# USB-TO-UART-BRIDGE.net
KiCad netlist of a schematic drawn in Altium Designer
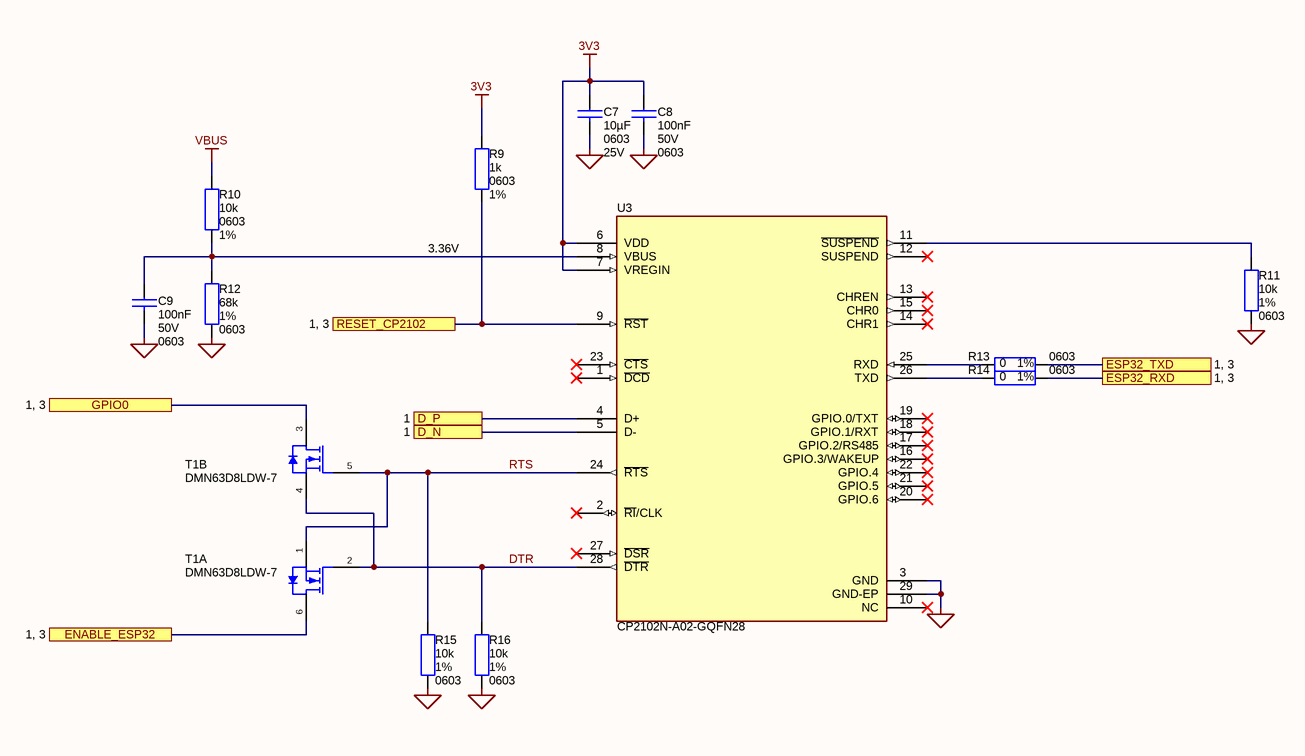
[diagram p0: USB-TO-UART-BRIDGE.SchDoc]

(export (version "E")
  (design (tool "Eeschema 10.0.6"))
  (components
    (comp (ref "C7")
      (value "10µF")
      (footprint "CAPC0603X37L")
      (description "CAPACITOR 10 µF 0603 X5R 25V 10%")
      (fields
        (field (name "MANUFACTURER 1 PART NUMBER") "GRM188R61E106KA73D")
        (field (name "CASE/PACKAGE") "0603")
        (field (name "VOLTAGE") "25V")
        (field (name "TOLERANCE") "10%")
        (field (name "COMMENT DESIGNER") "can be substituted same values other manufacturer")
      )
      (libsource (lib "EDATRON Solutions GmbH") (part "C"))
    )
    (comp (ref "C8")
      (value "100nF")
      (footprint "CAPC0603X37L")
      (description "CAPACITOR 100 nF 0603 X7R 50V 10%")
      (fields
        (field (name "VOLTAGE") "50V")
        (field (name "MANUFACTURER 1 PART NUMBER") "C0603C104K5RACTU")
        (field (name "TOLERANCE") "10%")
        (field (name "CASE/PACKAGE") "0603")
        (field (name "COMMENT DESIGNER") "can be substituted same values other manufacturer")
      )
      (libsource (lib "EDATRON Solutions GmbH") (part "C"))
    )
    (comp (ref "C9")
      (value "100nF")
      (footprint "CAPC0603X37L")
      (description "CAPACITOR 100 nF 0603 X7R 50V 10%")
      (fields
        (field (name "VOLTAGE") "50V")
        (field (name "MANUFACTURER 1 PART NUMBER") "C0603C104K5RACTU")
        (field (name "TOLERANCE") "10%")
        (field (name "CASE/PACKAGE") "0603")
        (field (name "COMMENT DESIGNER") "can be substituted same values other manufacturer")
      )
      (libsource (lib "EDATRON Solutions GmbH") (part "C"))
    )
    (comp (ref "R9")
      (value "1k")
      (footprint "RESC0603X21L")
      (description "RESISTOR 1K 1% 0603 100mW")
      (fields
        (field (name "CASE/PACKAGE") "0603")
        (field (name "MANUFACTURER 1 PART NUMBER") "RC0603FR-071KL")
        (field (name "POWER") "100mW")
        (field (name "TOLERANCE") "1%")
        (field (name "COMMENT DESIGNER") "can be substituted same values other manufacturers")
      )
      (libsource (lib "") (part "R_1"))
    )
    (comp (ref "R10")
      (value "10k")
      (footprint "RESC0603X21L")
      (description "RESISTOR 33K 1% 0603 100mW")
      (fields
        (field (name "MANUFACTURER 1 PART NUMBER") "RC0603FR-0733KL")
        (field (name "POWER") "100mW")
        (field (name "CASE/PACKAGE") "0603")
        (field (name "TOLERANCE") "1%")
        (field (name "COMMENT DESIGNER") "can be substituted same values other manufacturers")
      )
      (libsource (lib "") (part "R_1"))
    )
    (comp (ref "R11")
      (value "10k")
      (footprint "RESC0603X21L")
      (description "RESISTOR 10K 1% 0603 100mW")
      (fields
        (field (name "POWER") "100mW")
        (field (name "TOLERANCE") "1%")
        (field (name "CASE/PACKAGE") "0603")
        (field (name "MANUFACTURER 1 PART NUMBER") "RC0603FR-0710KL")
        (field (name "COMMENT DESIGNER") "can be substituted same values other manufacturers")
      )
      (libsource (lib "") (part "R_2"))
    )
    (comp (ref "R12")
      (value "68k")
      (footprint "RESC0603X21L")
      (description "RESISTOR 68K 1% 0603 100mW")
      (fields
        (field (name "TOLERANCE") "1%")
        (field (name "MANUFACTURER 1 PART NUMBER") "RC0603FR-0768KL")
        (field (name "POWER") "100mW")
        (field (name "CASE/PACKAGE") "0603")
        (field (name "COMMENT DESIGNER") "can be substituted same values other manufacturers")
      )
      (libsource (lib "") (part "R_1"))
    )
    (comp (ref "R13")
      (value "0")
      (footprint "RESC0603X21L")
      (description "RESISTOR 0R 1% 0603 100mW")
      (fields
        (field (name "POWER") "100mW")
        (field (name "CASE/PACKAGE") "0603")
        (field (name "MANUFACTURER 1 PART NUMBER") "RC0603FR-070RL")
        (field (name "TOLERANCE") "1%")
        (field (name "COMMENT DESIGNER") "can be substituted same values other manufacturers")
      )
      (libsource (lib "EDATRON Solutions GmbH") (part "R"))
    )
    (comp (ref "R14")
      (value "0")
      (footprint "RESC0603X21L")
      (description "RESISTOR 0R 1% 0603 100mW")
      (fields
        (field (name "POWER") "100mW")
        (field (name "CASE/PACKAGE") "0603")
        (field (name "MANUFACTURER 1 PART NUMBER") "RC0603FR-070RL")
        (field (name "TOLERANCE") "1%")
        (field (name "COMMENT DESIGNER") "can be substituted same values other manufacturers")
      )
      (libsource (lib "EDATRON Solutions GmbH") (part "R"))
    )
    (comp (ref "R15")
      (value "10k")
      (footprint "RESC0603X21L")
      (description "RESISTOR 10K 1% 0603 100mW")
      (fields
        (field (name "POWER") "100mW")
        (field (name "TOLERANCE") "1%")
        (field (name "CASE/PACKAGE") "0603")
        (field (name "MANUFACTURER 1 PART NUMBER") "RC0603FR-0710KL")
        (field (name "COMMENT DESIGNER") "can be substituted same values other manufacturers")
      )
      (libsource (lib "") (part "R_2"))
    )
    (comp (ref "R16")
      (value "10k")
      (footprint "RESC0603X21L")
      (description "RESISTOR 10K 1% 0603 100mW")
      (fields
        (field (name "POWER") "100mW")
        (field (name "TOLERANCE") "1%")
        (field (name "CASE/PACKAGE") "0603")
        (field (name "MANUFACTURER 1 PART NUMBER") "RC0603FR-0710KL")
        (field (name "COMMENT DESIGNER") "can be substituted same values other manufacturers")
      )
      (libsource (lib "") (part "R_2"))
    )
    (comp (ref "T1")
      (value "DMN63D8LDW-7")
      (footprint "SOT23-6P65_210X110L32X20")
      (fields (field (name "POWER") "400"))
      (libsource (lib "EDATRON Solutions GmbH") (part "DUAL-MOSFET-N"))
    )
    (comp (ref "U3")
      (value "CP2102N-A02-GQFN28")
      (footprint "CP2102N-A02-GQFN28-Footprint-1")
      (description "USB-IC-Schnittstelle USBXpress - USB to UART Bridge QFN28")
      (libsource (lib "EDATRON Solutions GmbH") (part "CP2102N-A02-GQFN28"))
    )
  )
  (nets
    (net (code "1") (name "/DTR") (class "Default")
      (node (ref "R16") (pin "2") (pinfunction "2_2") (pintype "passive"))
      (node (ref "T1") (pin "2") (pinfunction "G1_2") (pintype "passive"))
      (node (ref "T1") (pin "4") (pinfunction "S2_4") (pintype "passive"))
      (node (ref "U3") (pin "28") (pinfunction "~{DTR}_28") (pintype "output"))
    )
    (net (code "2") (name "/D_N") (class "Default")
      (node (ref "U3") (pin "5") (pinfunction "D-_5") (pintype "passive"))
    )
    (net (code "3") (name "/D_P") (class "Default")
      (node (ref "U3") (pin "4") (pinfunction "D+_4") (pintype "passive"))
    )
    (net (code "4") (name "/ENABLE_ESP32") (class "Default")
      (node (ref "T1") (pin "6") (pinfunction "D1_6") (pintype "passive"))
    )
    (net (code "5") (name "/ESP32_RXD") (class "Default")
      (node (ref "R14") (pin "1") (pinfunction "1_1") (pintype "passive"))
    )
    (net (code "6") (name "/ESP32_TXD") (class "Default")
      (node (ref "R13") (pin "1") (pinfunction "1_1") (pintype "passive"))
    )
    (net (code "7") (name "/GPIO0") (class "Default")
      (node (ref "T1") (pin "3") (pinfunction "D2_3") (pintype "passive"))
    )
    (net (code "8") (name "/RESET_CP2102") (class "Default")
      (node (ref "R9") (pin "2") (pinfunction "2_2") (pintype "passive"))
      (node (ref "U3") (pin "9") (pinfunction "~{RST}_9") (pintype "input"))
    )
    (net (code "9") (name "/RTS") (class "Default")
      (node (ref "R15") (pin "2") (pinfunction "2_2") (pintype "passive"))
      (node (ref "T1") (pin "1") (pinfunction "S1_1") (pintype "passive"))
      (node (ref "T1") (pin "5") (pinfunction "G2_5") (pintype "passive"))
      (node (ref "U3") (pin "24") (pinfunction "~{RTS}_24") (pintype "output"))
    )
    (net (code "10") (name "3V3") (class "Default")
      (node (ref "C7") (pin "1") (pinfunction "1_1") (pintype "passive"))
      (node (ref "C8") (pin "1") (pinfunction "1_1") (pintype "passive"))
      (node (ref "R9") (pin "1") (pinfunction "1_1") (pintype "passive"))
      (node (ref "U3") (pin "6") (pinfunction "VDD_6") (pintype "power_in"))
      (node (ref "U3") (pin "7") (pinfunction "VREGIN_7") (pintype "input"))
    )
    (net (code "11") (name "GND") (class "Default")
      (node (ref "C7") (pin "2") (pinfunction "2_2") (pintype "passive"))
      (node (ref "C8") (pin "2") (pinfunction "2_2") (pintype "passive"))
      (node (ref "C9") (pin "2") (pinfunction "2_2") (pintype "passive"))
      (node (ref "R11") (pin "1") (pinfunction "1_1") (pintype "passive"))
      (node (ref "R12") (pin "2") (pinfunction "2_2") (pintype "passive"))
      (node (ref "R15") (pin "1") (pinfunction "1_1") (pintype "passive"))
      (node (ref "R16") (pin "1") (pinfunction "1_1") (pintype "passive"))
      (node (ref "U3") (pin "29") (pinfunction "GND-EP_29") (pintype "power_in"))
      (node (ref "U3") (pin "3") (pinfunction "GND_3") (pintype "power_in"))
    )
    (net (code "12") (name "Net-(U3-RXD)") (class "Default")
      (node (ref "R13") (pin "2") (pinfunction "2_2") (pintype "passive"))
      (node (ref "U3") (pin "25") (pinfunction "RXD_25") (pintype "input"))
    )
    (net (code "13") (name "Net-(U3-TXD)") (class "Default")
      (node (ref "R14") (pin "2") (pinfunction "2_2") (pintype "passive"))
      (node (ref "U3") (pin "26") (pinfunction "TXD_26") (pintype "output"))
    )
    (net (code "14") (name "Net-(U3-VBUS)") (class "Default")
      (node (ref "C9") (pin "1") (pinfunction "1_1") (pintype "passive"))
      (node (ref "R10") (pin "2") (pinfunction "2_2") (pintype "passive"))
      (node (ref "R12") (pin "1") (pinfunction "1_1") (pintype "passive"))
      (node (ref "U3") (pin "8") (pinfunction "VBUS_8") (pintype "input"))
    )
    (net (code "15") (name "Net-(U3-~{SUSPEND})") (class "Default")
      (node (ref "R11") (pin "2") (pinfunction "2_2") (pintype "passive"))
      (node (ref "U3") (pin "11") (pinfunction "~{SUSPEND}_11") (pintype "output"))
    )
    (net (code "16") (name "VBUS") (class "Default")
      (node (ref "R10") (pin "1") (pinfunction "1_1") (pintype "passive"))
    )
    (net (code "17") (name "unconnected-(U3-CHR0-Pad15)") (class "Default")
      (node (ref "U3") (pin "15") (pinfunction "CHR0_15") (pintype "output+no_connect"))
    )
    (net (code "18") (name "unconnected-(U3-CHR1-Pad14)") (class "Default")
      (node (ref "U3") (pin "14") (pinfunction "CHR1_14") (pintype "output+no_connect"))
    )
    (net (code "19") (name "unconnected-(U3-CHREN-Pad13)") (class "Default")
      (node (ref "U3") (pin "13") (pinfunction "CHREN_13") (pintype "output+no_connect"))
    )
    (net (code "20") (name "unconnected-(U3-GPIO.0{slash}TXT-Pad19)") (class "Default")
      (node (ref "U3") (pin "19") (pinfunction "GPIO.0/TXT_19") (pintype "bidirectional+no_connect"))
    )
    (net (code "21") (name "unconnected-(U3-GPIO.1{slash}RXT-Pad18)") (class "Default")
      (node (ref "U3") (pin "18") (pinfunction "GPIO.1/RXT_18") (pintype "bidirectional+no_connect"))
    )
    (net (code "22") (name "unconnected-(U3-GPIO.2{slash}RS485-Pad17)") (class "Default")
      (node (ref "U3") (pin "17") (pinfunction "GPIO.2/RS485_17") (pintype "bidirectional+no_connect"))
    )
    (net (code "23") (name "unconnected-(U3-GPIO.3{slash}WAKEUP-Pad16)") (class "Default")
      (node (ref "U3") (pin "16") (pinfunction "GPIO.3/WAKEUP_16") (pintype "bidirectional+no_connect"))
    )
    (net (code "24") (name "unconnected-(U3-GPIO.4-Pad22)") (class "Default")
      (node (ref "U3") (pin "22") (pinfunction "GPIO.4_22") (pintype "bidirectional+no_connect"))
    )
    (net (code "25") (name "unconnected-(U3-GPIO.5-Pad21)") (class "Default")
      (node (ref "U3") (pin "21") (pinfunction "GPIO.5_21") (pintype "bidirectional+no_connect"))
    )
    (net (code "26") (name "unconnected-(U3-GPIO.6-Pad20)") (class "Default")
      (node (ref "U3") (pin "20") (pinfunction "GPIO.6_20") (pintype "bidirectional+no_connect"))
    )
    (net (code "27") (name "unconnected-(U3-NC-Pad10)") (class "Default")
      (node (ref "U3") (pin "10") (pinfunction "NC_10") (pintype "passive+no_connect"))
    )
    (net (code "28") (name "unconnected-(U3-SUSPEND-Pad12)") (class "Default")
      (node (ref "U3") (pin "12") (pinfunction "SUSPEND_12") (pintype "output+no_connect"))
    )
    (net (code "29") (name "unconnected-(U3-~{CTS}-Pad23)") (class "Default")
      (node (ref "U3") (pin "23") (pinfunction "~{CTS}_23") (pintype "input+no_connect"))
    )
    (net (code "30") (name "unconnected-(U3-~{DCD}-Pad1)") (class "Default")
      (node (ref "U3") (pin "1") (pinfunction "~{DCD}_1") (pintype "input+no_connect"))
    )
    (net (code "31") (name "unconnected-(U3-~{DSR}-Pad27)") (class "Default")
      (node (ref "U3") (pin "27") (pinfunction "~{DSR}_27") (pintype "input+no_connect"))
    )
    (net (code "32") (name "unconnected-(U3-~{RI}{slash}CLK-Pad2)") (class "Default")
      (node (ref "U3") (pin "2") (pinfunction "~{RI}/CLK_2") (pintype "bidirectional+no_connect"))
    )
  )
)
